# AEMLIC_V4.net
KiCad netlist of a schematic drawn in EAGLE
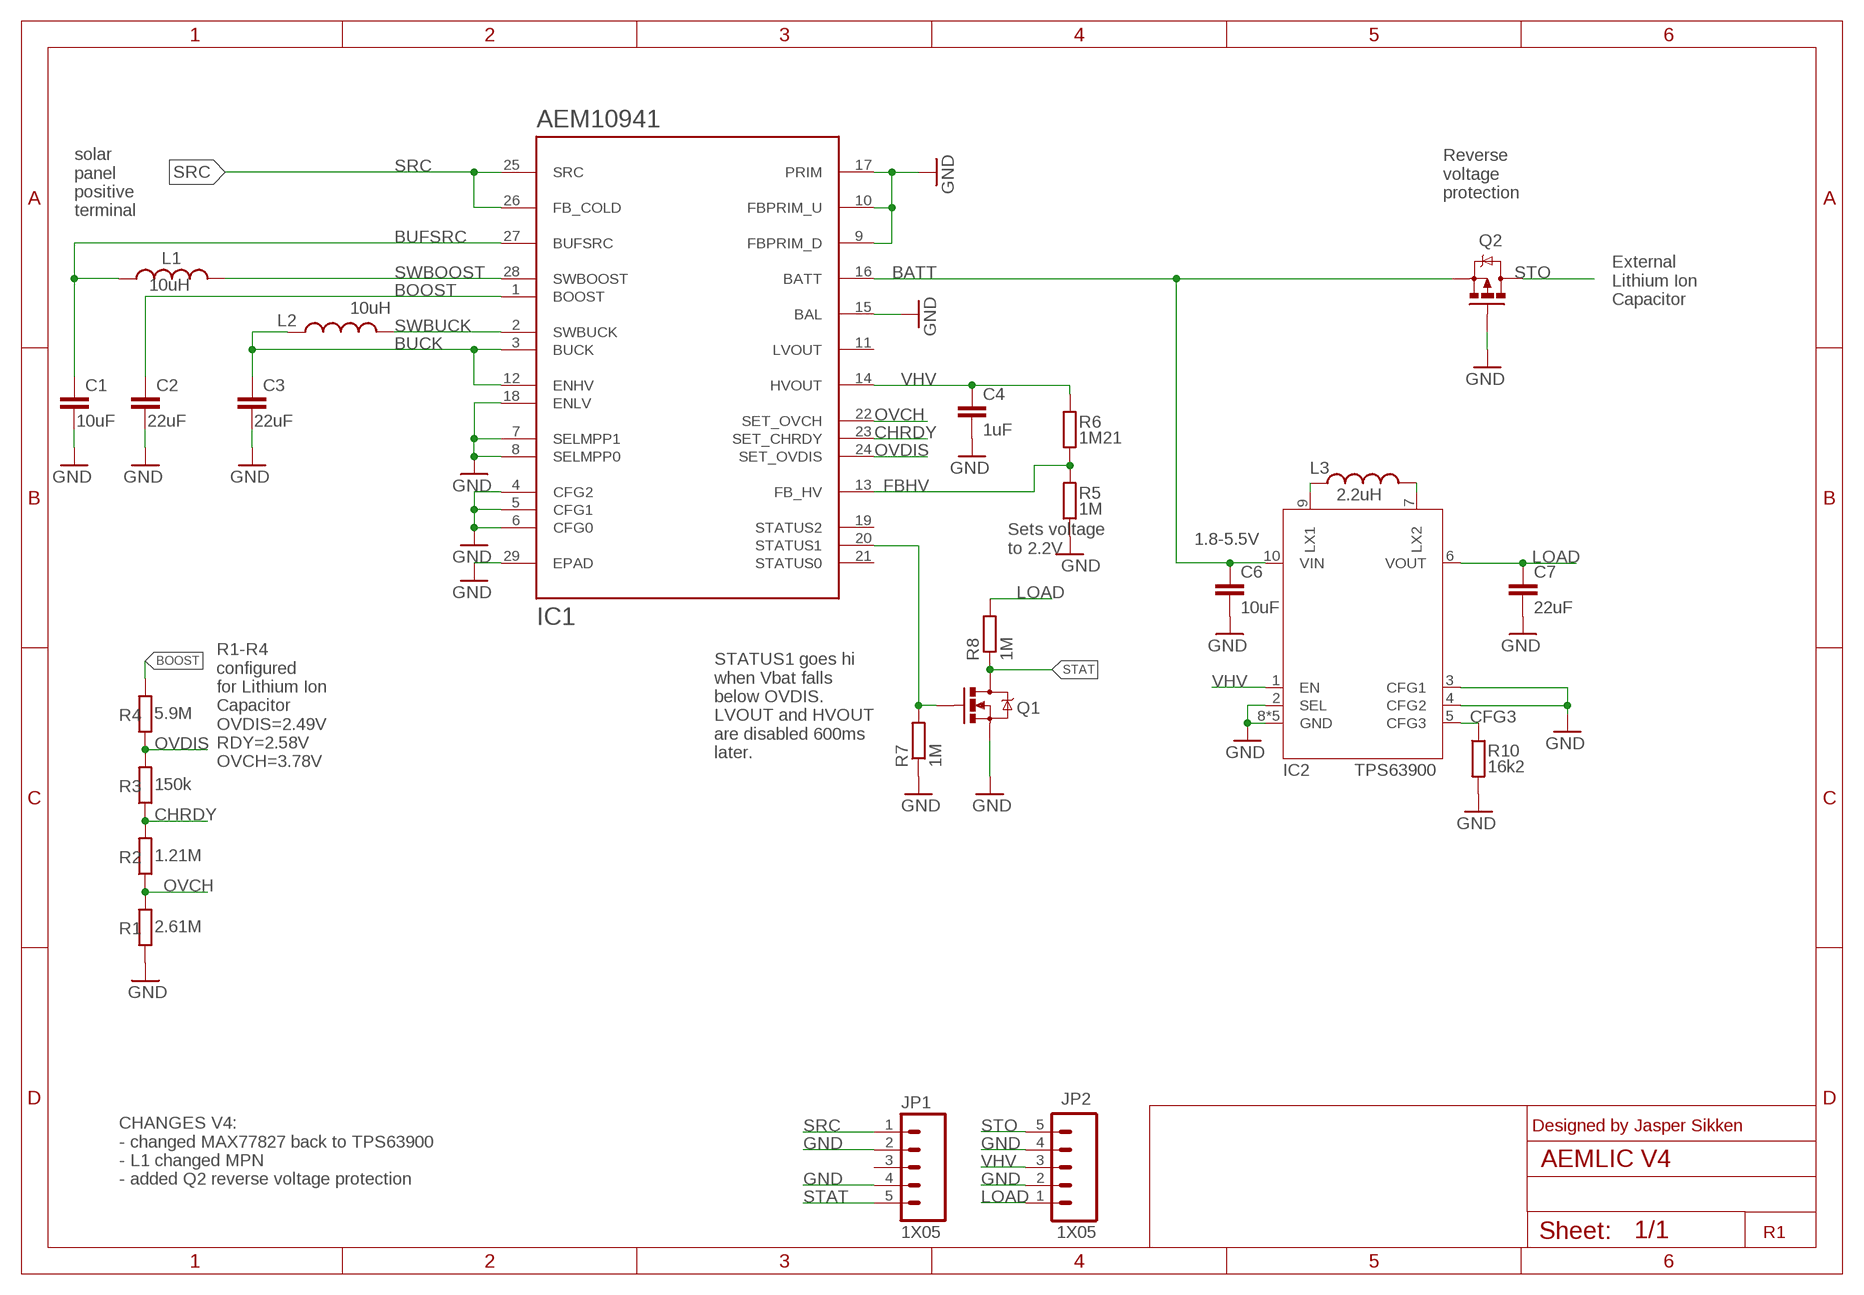
[diagram p0: schematic, sheet 1]

(export (version "E")
  (design (tool "Eeschema 10.0.6"))
  (components
    (comp (ref "C1")
      (value "10uF")
      (footprint "eagle-import:C0603")
      (fields
        (field (name "MF") "Taiyo Yuden")
        (field (name "MPN") "LMK107BBJ106MALT")
        (field (name "MF_1") "KEYSTONE")
        (field (name "MPN_1") "1049P")
      )
      (libsource (lib "eagle-import") (part "TSEM_C0603_10UF"))
    )
    (comp (ref "C2")
      (value "22uF")
      (footprint "eagle-import:C0603")
      (fields
        (field (name "MF") "Murata")
        (field (name "MPN") "GRM188R61A226ME15D")
        (field (name "MF_1") "TDK")
        (field (name "MPN_1") "CGA5L1X7S1A226M160AC")
      )
      (libsource (lib "eagle-import") (part "TSEM_C0603_22UF"))
    )
    (comp (ref "C3")
      (value "22uF")
      (footprint "eagle-import:C0603")
      (fields
        (field (name "MF") "Taiyo Yuden")
        (field (name "MPN") "LMK107BBJ106MALT")
        (field (name "MF_1") "KEYSTONE")
        (field (name "MPN_1") "1049P")
      )
      (libsource (lib "eagle-import") (part "TSEM_C0603_10UF"))
    )
    (comp (ref "C4")
      (value "1uF")
      (footprint "eagle-import:C0603")
      (fields (field (name "MF") "Taiyo Yuden") (field (name "MPN") "LMK107BBJ106MALT"))
      (libsource (lib "eagle-import") (part "TSEM_C0603_10UF"))
    )
    (comp (ref "C6")
      (value "10uF")
      (footprint "eagle-import:C0603")
      (fields (field (name "MF") "Taiyo Yuden") (field (name "MPN") "LMK107BBJ106MALT"))
      (libsource (lib "eagle-import") (part "C0603_10UF"))
    )
    (comp (ref "C7")
      (value "22uF")
      (footprint "eagle-import:C0603")
      (fields (field (name "MF") "Murata") (field (name "MPN") "GRM188R61A226ME15D"))
      (libsource (lib "eagle-import") (part "C0603_22UF"))
    )
    (comp (ref "IC1")
      (value "AEM10941")
      (footprint "eagle-import:QFN50P505X505X90-28")
      (fields (field (name "MF") "e-peas"))
      (libsource (lib "eagle-import") (part "AEM10941"))
    )
    (comp (ref "IC2")
      (value "TPS63900")
      (footprint "eagle-import:WSON10")
      (libsource (lib "eagle-import") (part "TPS63900"))
    )
    (comp (ref "JP1")
      (value "1X05")
      (footprint "eagle-import:1X05_2.54MM_ROUND_NOSILK")
      (libsource (lib "eagle-import") (part "1X05"))
    )
    (comp (ref "JP2")
      (value "1X05")
      (footprint "eagle-import:1X05_2.54MM_ROUND_NOSILK")
      (libsource (lib "eagle-import") (part "1X05"))
    )
    (comp (ref "L1")
      (value "10uH")
      (footprint "eagle-import:L_3225MM")
      (fields (field (name "MF") "Murata") (field (name "MPN") "DFE322512F-100M=P2"))
      (libsource (lib "eagle-import") (part "L4"))
    )
    (comp (ref "L2")
      (value "10uH")
      (footprint "eagle-import:L0603")
      (fields
        (field (name "MF") "TDK")
        (field (name "MPN") "MLZ1608M100WT")
        (field (name "MF_1") "TAIYO YUDEN")
        (field (name "MPN_1") "CK2125100M-T")
      )
      (libsource (lib "eagle-import") (part "TSEM_L0603_10UH"))
    )
    (comp (ref "L3")
      (value "2.2uH")
      (footprint "eagle-import:L_1008_[2520]")
      (fields (field (name "MF") "Murata") (field (name "MPN") "DFE252012F-2R2M=P2"))
      (libsource (lib "eagle-import") (part "TSEM_L2"))
    )
    (comp (ref "Q1")
      (value "DMG1012UW")
      (footprint "eagle-import:SOT323")
      (fields (field (name "MF") "Diodes") (field (name "MPN") "DMG1012UW-7"))
      (libsource (lib "eagle-import") (part "MOSFET-N-CHANNEL_DMG1012UW"))
    )
    (comp (ref "Q2")
      (value "DMP2160UW")
      (footprint "eagle-import:SOT323")
      (libsource (lib "eagle-import") (part "MOSFET-P-CHANNEL-DMP2160UW"))
    )
    (comp (ref "R1")
      (value "2.61M")
      (footprint "eagle-import:R0402")
      (fields (field (name "MF") "Walsin") (field (name "MPN") "WR04X1004FTL"))
      (libsource (lib "eagle-import") (part "TSEM_R0402_1M"))
    )
    (comp (ref "R2")
      (value "1.21M")
      (footprint "eagle-import:R0402")
      (fields (field (name "MF") "Walsin") (field (name "MPN") "WR04X1004FTL"))
      (libsource (lib "eagle-import") (part "TSEM_R0402_1M"))
    )
    (comp (ref "R3")
      (value "150k")
      (footprint "eagle-import:R0402")
      (fields (field (name "MF") "Walsin") (field (name "MPN") "WR04X1004FTL"))
      (libsource (lib "eagle-import") (part "TSEM_R0402_1M"))
    )
    (comp (ref "R4")
      (value "5.9M")
      (footprint "eagle-import:R0402")
      (fields (field (name "MF") "Walsin") (field (name "MPN") "WR04X1004FTL"))
      (libsource (lib "eagle-import") (part "TSEM_R0402_1M"))
    )
    (comp (ref "R5")
      (value "1M")
      (footprint "eagle-import:R0402")
      (fields (field (name "MF") "Walsin") (field (name "MPN") "WR04X1004FTL"))
      (libsource (lib "eagle-import") (part "TSEM_R0402_1M"))
    )
    (comp (ref "R6")
      (value "1M21")
      (footprint "eagle-import:R0402")
      (fields (field (name "MF") "Walsin") (field (name "MPN") "WR04X1004FTL"))
      (libsource (lib "eagle-import") (part "TSEM_R0402_1M"))
    )
    (comp (ref "R7")
      (value "1M")
      (footprint "eagle-import:R0402")
      (fields (field (name "MF") "Walsin") (field (name "MPN") "WR04X1004FTL"))
      (libsource (lib "eagle-import") (part "TSEM_R0402_1M"))
    )
    (comp (ref "R8")
      (value "1M")
      (footprint "eagle-import:R0402")
      (fields (field (name "MF") "Walsin") (field (name "MPN") "WR04X1004FTL"))
      (libsource (lib "eagle-import") (part "TSEM_R0402_1M"))
    )
    (comp (ref "R10")
      (value "16k2")
      (footprint "eagle-import:R0402")
      (libsource (lib "eagle-import") (part "R0402_10K"))
    )
  )
  (nets
    (net (code "1") (name "/BATT") (class "Default")
      (node (ref "C6") (pin "1") (pinfunction "1_1") (pintype "passive"))
      (node (ref "IC1") (pin "16") (pinfunction "BATT_16") (pintype "bidirectional"))
      (node (ref "IC2") (pin "10") (pinfunction "VIN_10") (pintype "bidirectional"))
      (node (ref "Q2") (pin "2") (pinfunction "S_2") (pintype "passive"))
    )
    (net (code "2") (name "/BUCK") (class "Default")
      (node (ref "C3") (pin "1") (pinfunction "1_1") (pintype "passive"))
      (node (ref "IC1") (pin "12") (pinfunction "ENHV_12") (pintype "bidirectional"))
      (node (ref "IC1") (pin "3") (pinfunction "BUCK_3") (pintype "bidirectional"))
      (node (ref "L2") (pin "1") (pinfunction "1_1") (pintype "passive"))
    )
    (net (code "3") (name "/BUFSRC") (class "Default")
      (node (ref "C1") (pin "1") (pinfunction "1_1") (pintype "passive"))
      (node (ref "IC1") (pin "27") (pinfunction "BUFSRC_27") (pintype "power_in"))
      (node (ref "L1") (pin "1") (pinfunction "1_1") (pintype "passive"))
    )
    (net (code "4") (name "/CFG3") (class "Default")
      (node (ref "IC2") (pin "5") (pinfunction "CFG3_5") (pintype "bidirectional"))
      (node (ref "R10") (pin "1") (pinfunction "1_1") (pintype "passive"))
    )
    (net (code "5") (name "/CHRDY") (class "Default")
      (node (ref "IC1") (pin "23") (pinfunction "SET_CHRDY_23") (pintype "bidirectional"))
      (node (ref "R2") (pin "2") (pinfunction "2_2") (pintype "passive"))
      (node (ref "R3") (pin "1") (pinfunction "1_1") (pintype "passive"))
    )
    (net (code "6") (name "/FBHV") (class "Default")
      (node (ref "IC1") (pin "13") (pinfunction "FB_HV_13") (pintype "bidirectional"))
      (node (ref "R5") (pin "2") (pinfunction "2_2") (pintype "passive"))
      (node (ref "R6") (pin "1") (pinfunction "1_1") (pintype "passive"))
    )
    (net (code "7") (name "/LOAD") (class "Default")
      (node (ref "C7") (pin "1") (pinfunction "1_1") (pintype "passive"))
      (node (ref "IC2") (pin "6") (pinfunction "VOUT_6") (pintype "bidirectional"))
      (node (ref "JP2") (pin "1") (pinfunction "1_1") (pintype "passive"))
      (node (ref "R8") (pin "2") (pinfunction "2_2") (pintype "passive"))
    )
    (net (code "8") (name "/OVCH") (class "Default")
      (node (ref "IC1") (pin "22") (pinfunction "SET_OVCH_22") (pintype "bidirectional"))
      (node (ref "R1") (pin "2") (pinfunction "2_2") (pintype "passive"))
      (node (ref "R2") (pin "1") (pinfunction "1_1") (pintype "passive"))
    )
    (net (code "9") (name "/OVDIS") (class "Default")
      (node (ref "IC1") (pin "24") (pinfunction "SET_OVDIS_24") (pintype "bidirectional"))
      (node (ref "R3") (pin "2") (pinfunction "2_2") (pintype "passive"))
      (node (ref "R4") (pin "1") (pinfunction "1_1") (pintype "passive"))
    )
    (net (code "10") (name "/STO") (class "Default")
      (node (ref "JP2") (pin "5") (pinfunction "5_5") (pintype "passive"))
      (node (ref "Q2") (pin "3") (pinfunction "D_3") (pintype "passive"))
    )
    (net (code "11") (name "/SWBOOST") (class "Default")
      (node (ref "IC1") (pin "28") (pinfunction "SWBOOST_28") (pintype "power_in"))
      (node (ref "L1") (pin "2") (pinfunction "2_2") (pintype "passive"))
    )
    (net (code "12") (name "/SWBUCK") (class "Default")
      (node (ref "IC1") (pin "2") (pinfunction "SWBUCK_2") (pintype "bidirectional"))
      (node (ref "L2") (pin "2") (pinfunction "2_2") (pintype "passive"))
    )
    (net (code "13") (name "/VHV") (class "Default")
      (node (ref "C4") (pin "1") (pinfunction "1_1") (pintype "passive"))
      (node (ref "IC1") (pin "14") (pinfunction "HVOUT_14") (pintype "bidirectional"))
      (node (ref "IC2") (pin "1") (pinfunction "EN_1") (pintype "bidirectional"))
      (node (ref "JP2") (pin "3") (pinfunction "3_3") (pintype "passive"))
      (node (ref "R6") (pin "2") (pinfunction "2_2") (pintype "passive"))
    )
    (net (code "14") (name "BOOST") (class "Default")
      (node (ref "C2") (pin "1") (pinfunction "1_1") (pintype "passive"))
      (node (ref "IC1") (pin "1") (pinfunction "BOOST_1") (pintype "bidirectional"))
      (node (ref "R4") (pin "2") (pinfunction "2_2") (pintype "passive"))
    )
    (net (code "15") (name "GND") (class "Default")
      (node (ref "C1") (pin "2") (pinfunction "2_2") (pintype "passive"))
      (node (ref "C2") (pin "2") (pinfunction "2_2") (pintype "passive"))
      (node (ref "C3") (pin "2") (pinfunction "2_2") (pintype "passive"))
      (node (ref "C4") (pin "2") (pinfunction "2_2") (pintype "passive"))
      (node (ref "C6") (pin "2") (pinfunction "2_2") (pintype "passive"))
      (node (ref "C7") (pin "2") (pinfunction "2_2") (pintype "passive"))
      (node (ref "IC1") (pin "10") (pinfunction "FBPRIM_U_10") (pintype "bidirectional"))
      (node (ref "IC1") (pin "15") (pinfunction "BAL_15") (pintype "bidirectional"))
      (node (ref "IC1") (pin "17") (pinfunction "PRIM_17") (pintype "bidirectional"))
      (node (ref "IC1") (pin "18") (pinfunction "ENLV_18") (pintype "bidirectional"))
      (node (ref "IC1") (pin "29") (pinfunction "EPAD_29") (pintype "power_in"))
      (node (ref "IC1") (pin "4") (pinfunction "CFG2_4") (pintype "bidirectional"))
      (node (ref "IC1") (pin "5") (pinfunction "CFG1_5") (pintype "bidirectional"))
      (node (ref "IC1") (pin "6") (pinfunction "CFG0_6") (pintype "bidirectional"))
      (node (ref "IC1") (pin "7") (pinfunction "SELMPP1_7") (pintype "bidirectional"))
      (node (ref "IC1") (pin "8") (pinfunction "SELMPP0_8") (pintype "bidirectional"))
      (node (ref "IC1") (pin "9") (pinfunction "FBPRIM_D_9") (pintype "bidirectional"))
      (node (ref "IC2") (pin "2") (pinfunction "SEL_2") (pintype "bidirectional"))
      (node (ref "IC2") (pin "29") (pinfunction "GND_29") (pintype "bidirectional"))
      (node (ref "IC2") (pin "3") (pinfunction "CFG1_3") (pintype "bidirectional"))
      (node (ref "IC2") (pin "4") (pinfunction "CFG2_4") (pintype "bidirectional"))
      (node (ref "IC2") (pin "8") (pinfunction "GND_8") (pintype "bidirectional"))
      (node (ref "IC2") (pin "P$2") (pinfunction "GND_P$2") (pintype "bidirectional"))
      (node (ref "IC2") (pin "P$4") (pinfunction "GND_P$4") (pintype "bidirectional"))
      (node (ref "IC2") (pin "P$5") (pinfunction "GND_P$5") (pintype "bidirectional"))
      (node (ref "JP1") (pin "2") (pinfunction "2_2") (pintype "passive"))
      (node (ref "JP1") (pin "4") (pinfunction "4_4") (pintype "passive"))
      (node (ref "JP2") (pin "2") (pinfunction "2_2") (pintype "passive"))
      (node (ref "JP2") (pin "4") (pinfunction "4_4") (pintype "passive"))
      (node (ref "Q1") (pin "2") (pinfunction "S_2") (pintype "passive"))
      (node (ref "Q2") (pin "1") (pinfunction "G_1") (pintype "passive"))
      (node (ref "R1") (pin "1") (pinfunction "1_1") (pintype "passive"))
      (node (ref "R10") (pin "2") (pinfunction "2_2") (pintype "passive"))
      (node (ref "R5") (pin "1") (pinfunction "1_1") (pintype "passive"))
      (node (ref "R7") (pin "1") (pinfunction "1_1") (pintype "passive"))
    )
    (net (code "16") (name "Net-(IC1-STATUS1)") (class "Default")
      (node (ref "IC1") (pin "20") (pinfunction "STATUS1_20") (pintype "bidirectional"))
      (node (ref "Q1") (pin "1") (pinfunction "G_1") (pintype "passive"))
      (node (ref "R7") (pin "2") (pinfunction "2_2") (pintype "passive"))
    )
    (net (code "17") (name "Net-(IC2-LX1)") (class "Default")
      (node (ref "IC2") (pin "9") (pinfunction "LX1_9") (pintype "bidirectional"))
      (node (ref "L3") (pin "1") (pinfunction "1_1") (pintype "passive"))
    )
    (net (code "18") (name "Net-(IC2-LX2)") (class "Default")
      (node (ref "IC2") (pin "7") (pinfunction "LX2_7") (pintype "bidirectional"))
      (node (ref "L3") (pin "2") (pinfunction "2_2") (pintype "passive"))
    )
    (net (code "19") (name "SRC") (class "Default")
      (node (ref "IC1") (pin "25") (pinfunction "SRC_25") (pintype "power_in"))
      (node (ref "IC1") (pin "26") (pinfunction "FB_COLD_26") (pintype "input"))
      (node (ref "JP1") (pin "1") (pinfunction "1_1") (pintype "passive"))
    )
    (net (code "20") (name "STAT") (class "Default")
      (node (ref "JP1") (pin "5") (pinfunction "5_5") (pintype "passive"))
      (node (ref "Q1") (pin "3") (pinfunction "D_3") (pintype "passive"))
      (node (ref "R8") (pin "1") (pinfunction "1_1") (pintype "passive"))
    )
    (net (code "21") (name "unconnected-(IC1-LVOUT-Pad11)") (class "Default")
      (node (ref "IC1") (pin "11") (pinfunction "LVOUT_11") (pintype "bidirectional"))
    )
    (net (code "22") (name "unconnected-(IC1-STATUS0-Pad21)") (class "Default")
      (node (ref "IC1") (pin "21") (pinfunction "STATUS0_21") (pintype "bidirectional"))
    )
    (net (code "23") (name "unconnected-(IC1-STATUS2-Pad19)") (class "Default")
      (node (ref "IC1") (pin "19") (pinfunction "STATUS2_19") (pintype "bidirectional"))
    )
    (net (code "24") (name "unconnected-(JP1-Pad3)") (class "Default")
      (node (ref "JP1") (pin "3") (pinfunction "3_3") (pintype "passive"))
    )
  )
)
